# GSB-S05-V00-PSU3V3.net
KiCad netlist of a schematic drawn in Altium Designer
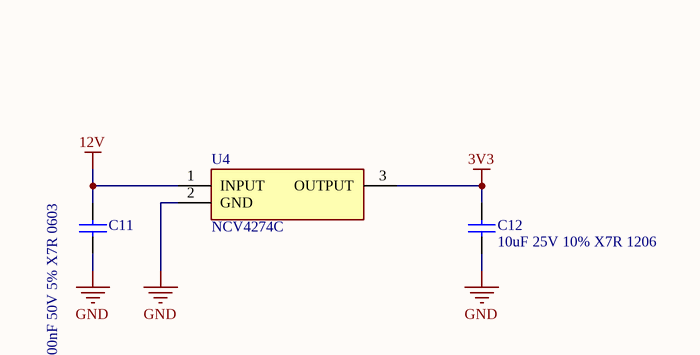
[diagram p0: GSB-S05-V00-PSU3V3.SchDoc]

(export (version "E")
  (design (tool "Eeschema 10.0.6"))
  (components
    (comp (ref "C11")
      (value "100nF 50V 5% X7R 0603")
      (footprint "Cap_Ceramic_0603")
      (description "Capacitor, Ceramic, SMD, 100nF, 50V, 5%, X7R, 0603")
      (libsource (lib "StandardCapacitors") (part "100nF 50V 5% X7R 0603"))
    )
    (comp (ref "C12")
      (value "10uF 25V 10% X7R 1206")
      (footprint "Cap_Ceramic_1206")
      (description "Capacitor, Ceramic, SMD, 10uF, 25V, 10%, X7R, 1206")
      (libsource (lib "StandardCapacitors") (part "10uF 25V 10% X7R 1206"))
    )
    (comp (ref "U4")
      (value "NCV4274C")
      (footprint "NCV4274CDT50RKG")
      (description "Integrated Circuit")
      (fields
        (field (name "MANUFACTURER_PART_NUMBER") "NCV4274CDT50RKG")
        (field (name "MOUSER PART NUMBER") "863-NCV4274CDT50RKG")
      )
      (libsource (lib "NCV4274CDT50RKG") (part "NCV4274C"))
    )
  )
  (nets
    (net (code "1") (name "3V3") (class "Default")
      (node (ref "C12") (pin "2") (pinfunction "2_2") (pintype "passive"))
      (node (ref "U4") (pin "3") (pinfunction "OUTPUT_3") (pintype "passive"))
    )
    (net (code "2") (name "12V") (class "Default")
      (node (ref "C11") (pin "2") (pinfunction "2_2") (pintype "passive"))
      (node (ref "U4") (pin "1") (pinfunction "INPUT_1") (pintype "passive"))
    )
    (net (code "3") (name "GND") (class "Default")
      (node (ref "C11") (pin "1") (pinfunction "1_1") (pintype "passive"))
      (node (ref "C12") (pin "1") (pinfunction "1_1") (pintype "passive"))
      (node (ref "U4") (pin "2") (pinfunction "GND_2") (pintype "passive"))
    )
  )
)
